# BQ25570EVO-206.net
KiCad netlist of a schematic drawn in Altium Designer
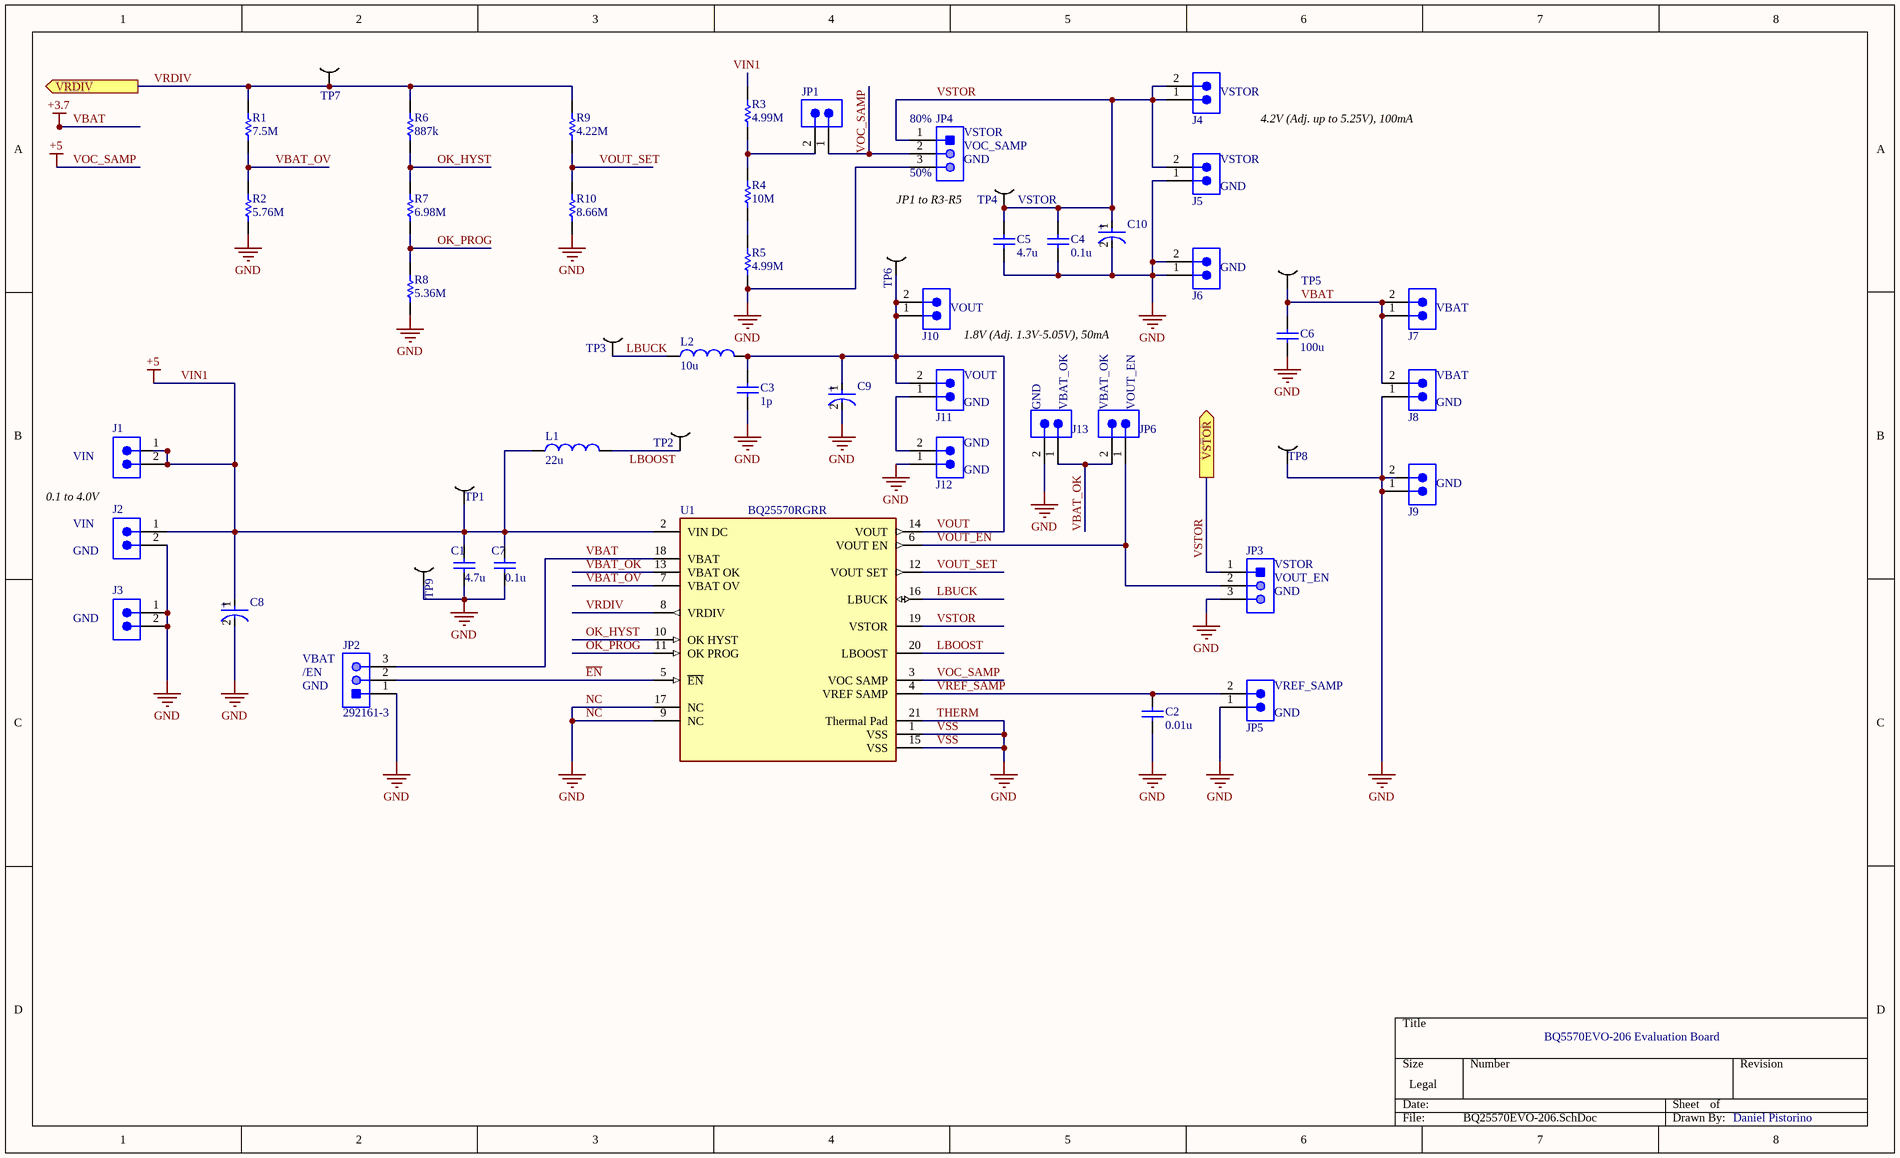
[diagram p0: BQ25570EVO-206.SchDoc]

(export (version "E")
  (design (tool "Eeschema 10.0.6"))
  (components
    (comp (ref "C1")
      (value "4.7u")
      (footprint "0603C")
      (description "Capacitor")
      (fields (field (name "Comment") "100nF") (field (name "PUBLISHER") "Altium Limited"))
      (libsource (lib "MB1136") (part "Cap"))
    )
    (comp (ref "C2")
      (value "0.01u")
      (description "Capacitor")
      (libsource (lib "Simulation Generic Components") (part "Capacitor"))
    )
    (comp (ref "C3")
      (value "1p")
      (description "Capacitor")
      (fields (field (name "Comment") "22u"))
      (libsource (lib "Simulation Generic Components") (part "Capacitor"))
    )
    (comp (ref "C4")
      (value "0.1u")
      (description "Capacitor")
      (libsource (lib "Simulation Generic Components") (part "Capacitor"))
    )
    (comp (ref "C5")
      (value "4.7u")
      (description "Capacitor")
      (libsource (lib "Simulation Generic Components") (part "Capacitor"))
    )
    (comp (ref "C6")
      (value "100u")
      (description "Capacitor")
      (libsource (lib "Simulation Generic Components") (part "Capacitor"))
    )
    (comp (ref "C7")
      (value "0.1u")
      (description "Capacitor")
      (libsource (lib "Simulation Generic Components") (part "Capacitor"))
    )
    (comp (ref "C8")
      (value "EEEFK1E470P")
      (footprint "FP-FKD-MFG")
      (description "CAP ALUM 47UF 20% 25V SMD")
      (fields (field (name "TOLERANCE") "20%") (field (name "VOLTAGE") "25V"))
      (libsource (lib "Altium Content Vault") (part "af6b09250824f1546b97fbd1c504875"))
    )
    (comp (ref "C9")
      (value "EEEFK1E470P")
      (footprint "FP-FKD-MFG")
      (description "CAP ALUM 47UF 20% 25V SMD")
      (fields (field (name "TOLERANCE") "20%") (field (name "VOLTAGE") "25V"))
      (libsource (lib "Altium Content Vault") (part "af6b09250824f1546b97fbd1c504875"))
    )
    (comp (ref "C10")
      (value "EEEFK1E470P")
      (footprint "FP-FKD-MFG")
      (description "CAP ALUM 47UF 20% 25V SMD")
      (fields (field (name "TOLERANCE") "20%") (field (name "VOLTAGE") "25V"))
      (libsource (lib "Altium Content Vault") (part "af6b09250824f1546b97fbd1c504875"))
    )
    (comp (ref "J1")
      (value "TSW-102-26-F-S")
      (footprint "SMTC-TSW-102-26-XX-S")
      (description "0.025\" SQ Post Header, Through-hole, Vertical, -55 to 125 degC, 2.54 mm Pitch, 2-Pin, Male, RoHS")
      (fields (field (name "MANUFACTURER") "Samtec"))
      (libsource (lib "Altium Content Vault") (part "SMTC-TSW-102-X-X-S-X"))
    )
    (comp (ref "J2")
      (value "TSW-102-26-F-S")
      (footprint "SMTC-TSW-102-26-XX-S")
      (description "0.025\" SQ Post Header, Through-hole, Vertical, -55 to 125 degC, 2.54 mm Pitch, 2-Pin, Male, RoHS")
      (fields (field (name "MANUFACTURER") "Samtec"))
      (libsource (lib "Altium Content Vault") (part "SMTC-TSW-102-X-X-S-X"))
    )
    (comp (ref "J3")
      (value "TSW-102-26-F-S")
      (footprint "SMTC-TSW-102-26-XX-S")
      (description "0.025\" SQ Post Header, Through-hole, Vertical, -55 to 125 degC, 2.54 mm Pitch, 2-Pin, Male, RoHS")
      (fields (field (name "MANUFACTURER") "Samtec"))
      (libsource (lib "Altium Content Vault") (part "SMTC-TSW-102-X-X-S-X"))
    )
    (comp (ref "J4")
      (value "TSW-102-26-F-S")
      (footprint "SMTC-TSW-102-26-XX-S")
      (description "0.025\" SQ Post Header, Through-hole, Vertical, -55 to 125 degC, 2.54 mm Pitch, 2-Pin, Male, RoHS")
      (fields (field (name "MANUFACTURER") "Samtec"))
      (libsource (lib "Altium Content Vault") (part "SMTC-TSW-102-X-X-S-X"))
    )
    (comp (ref "J5")
      (value "TSW-102-26-F-S")
      (footprint "SMTC-TSW-102-26-XX-S")
      (description "0.025\" SQ Post Header, Through-hole, Vertical, -55 to 125 degC, 2.54 mm Pitch, 2-Pin, Male, RoHS")
      (fields (field (name "MANUFACTURER") "Samtec"))
      (libsource (lib "Altium Content Vault") (part "SMTC-TSW-102-X-X-S-X"))
    )
    (comp (ref "J6")
      (value "TSW-102-26-F-S")
      (footprint "SMTC-TSW-102-26-XX-S")
      (description "0.025\" SQ Post Header, Through-hole, Vertical, -55 to 125 degC, 2.54 mm Pitch, 2-Pin, Male, RoHS")
      (fields (field (name "MANUFACTURER") "Samtec"))
      (libsource (lib "Altium Content Vault") (part "SMTC-TSW-102-X-X-S-X"))
    )
    (comp (ref "J7")
      (value "TSW-102-26-F-S")
      (footprint "SMTC-TSW-102-26-XX-S")
      (description "0.025\" SQ Post Header, Through-hole, Vertical, -55 to 125 degC, 2.54 mm Pitch, 2-Pin, Male, RoHS")
      (fields (field (name "MANUFACTURER") "Samtec"))
      (libsource (lib "Altium Content Vault") (part "SMTC-TSW-102-X-X-S-X"))
    )
    (comp (ref "J8")
      (value "TSW-102-26-F-S")
      (footprint "SMTC-TSW-102-26-XX-S")
      (description "0.025\" SQ Post Header, Through-hole, Vertical, -55 to 125 degC, 2.54 mm Pitch, 2-Pin, Male, RoHS")
      (fields (field (name "MANUFACTURER") "Samtec"))
      (libsource (lib "Altium Content Vault") (part "SMTC-TSW-102-X-X-S-X"))
    )
    (comp (ref "J9")
      (value "TSW-102-26-F-S")
      (footprint "SMTC-TSW-102-26-XX-S")
      (description "0.025\" SQ Post Header, Through-hole, Vertical, -55 to 125 degC, 2.54 mm Pitch, 2-Pin, Male, RoHS")
      (fields (field (name "MANUFACTURER") "Samtec"))
      (libsource (lib "Altium Content Vault") (part "SMTC-TSW-102-X-X-S-X"))
    )
    (comp (ref "J10")
      (value "TSW-102-26-F-S")
      (footprint "SMTC-TSW-102-26-XX-S")
      (description "0.025\" SQ Post Header, Through-hole, Vertical, -55 to 125 degC, 2.54 mm Pitch, 2-Pin, Male, RoHS")
      (fields (field (name "MANUFACTURER") "Samtec"))
      (libsource (lib "Altium Content Vault") (part "SMTC-TSW-102-X-X-S-X"))
    )
    (comp (ref "J11")
      (value "TSW-102-26-F-S")
      (footprint "SMTC-TSW-102-26-XX-S")
      (description "0.025\" SQ Post Header, Through-hole, Vertical, -55 to 125 degC, 2.54 mm Pitch, 2-Pin, Male, RoHS")
      (fields (field (name "MANUFACTURER") "Samtec"))
      (libsource (lib "Altium Content Vault") (part "SMTC-TSW-102-X-X-S-X"))
    )
    (comp (ref "J12")
      (value "TSW-102-26-F-S")
      (footprint "SMTC-TSW-102-26-XX-S")
      (description "0.025\" SQ Post Header, Through-hole, Vertical, -55 to 125 degC, 2.54 mm Pitch, 2-Pin, Male, RoHS")
      (fields (field (name "MANUFACTURER") "Samtec"))
      (libsource (lib "Altium Content Vault") (part "SMTC-TSW-102-X-X-S-X"))
    )
    (comp (ref "J13")
      (value "TSW-102-26-F-S")
      (footprint "SMTC-TSW-102-26-XX-S")
      (description "0.025\" SQ Post Header, Through-hole, Vertical, -55 to 125 degC, 2.54 mm Pitch, 2-Pin, Male, RoHS")
      (fields (field (name "MANUFACTURER") "Samtec"))
      (libsource (lib "Altium Content Vault") (part "SMTC-TSW-102-X-X-S-X"))
    )
    (comp (ref "JP1")
      (value "TSW-102-26-F-S")
      (footprint "SMTC-TSW-102-26-XX-S")
      (description "0.025\" SQ Post Header, Through-hole, Vertical, -55 to 125 degC, 2.54 mm Pitch, 2-Pin, Male, RoHS")
      (fields (field (name "MANUFACTURER") "Samtec"))
      (libsource (lib "Altium Content Vault") (part "SMTC-TSW-102-X-X-S-X"))
    )
    (comp (ref "JP2")
      (value "292161-3")
      (footprint "TECO-292161-3_V")
      (fields (field (name "MANUFACTURER") "TE Connectivity"))
      (libsource (lib "") (part "CN-1P-M-R3_1"))
    )
    (comp (ref "JP3")
      (value "292161-3")
      (footprint "TECO-292161-3_V")
      (fields (field (name "MANUFACTURER") "TE Connectivity"))
      (libsource (lib "Altium Content Vault") (part "CN-1P-M-R3"))
    )
    (comp (ref "JP4")
      (value "292161-3")
      (footprint "TECO-292161-3_V")
      (fields (field (name "MANUFACTURER") "TE Connectivity"))
      (libsource (lib "Altium Content Vault") (part "CN-1P-M-R3"))
    )
    (comp (ref "JP5")
      (value "TSW-102-26-F-S")
      (footprint "SMTC-TSW-102-26-XX-S")
      (description "0.025\" SQ Post Header, Through-hole, Vertical, -55 to 125 degC, 2.54 mm Pitch, 2-Pin, Male, RoHS")
      (fields (field (name "MANUFACTURER") "Samtec"))
      (libsource (lib "Altium Content Vault") (part "SMTC-TSW-102-X-X-S-X"))
    )
    (comp (ref "JP6")
      (value "TSW-102-26-F-S")
      (footprint "SMTC-TSW-102-26-XX-S")
      (description "0.025\" SQ Post Header, Through-hole, Vertical, -55 to 125 degC, 2.54 mm Pitch, 2-Pin, Male, RoHS")
      (fields (field (name "MANUFACTURER") "Samtec"))
      (libsource (lib "Altium Content Vault") (part "SMTC-TSW-102-X-X-S-X"))
    )
    (comp (ref "L1")
      (value "22u")
      (footprint "WE-RFI_0805")
      (description "744760382A WE-RFI SMT Ferrite Inductor")
      (fields (field (name "TOLERANCE") "5%"))
      (libsource (lib "Altium Content Vault") (part "Inductor - 1"))
    )
    (comp (ref "L2")
      (value "10u")
      (footprint "WE-RFI_0805")
      (description "744760382A WE-RFI SMT Ferrite Inductor")
      (fields (field (name "TOLERANCE") "5%"))
      (libsource (lib "Altium Content Vault") (part "Inductor - 1"))
    )
    (comp (ref "R1")
      (value "7.5M")
      (footprint "0603R")
      (description "Resistor")
      (fields (field (name "PUBLISHER") "Altium Limited"))
      (libsource (lib "MB1136") (part "Res1"))
    )
    (comp (ref "R2")
      (value "5.76M")
      (footprint "0603R")
      (description "Resistor")
      (fields (field (name "PUBLISHER") "Altium Limited"))
      (libsource (lib "MB1136") (part "Res1"))
    )
    (comp (ref "R3")
      (value "4.99M")
      (footprint "0603R")
      (description "Resistor")
      (fields (field (name "PUBLISHER") "Altium Limited"))
      (libsource (lib "MB1136") (part "Res1"))
    )
    (comp (ref "R4")
      (value "10M")
      (footprint "0603R")
      (description "Resistor")
      (fields (field (name "PUBLISHER") "Altium Limited"))
      (libsource (lib "MB1136") (part "Res1"))
    )
    (comp (ref "R5")
      (value "4.99M")
      (footprint "0603R")
      (description "Resistor")
      (fields (field (name "PUBLISHER") "Altium Limited"))
      (libsource (lib "MB1136") (part "Res1"))
    )
    (comp (ref "R6")
      (value "887k")
      (footprint "0603R")
      (description "Resistor")
      (fields (field (name "PUBLISHER") "Altium Limited"))
      (libsource (lib "MB1136") (part "Res1"))
    )
    (comp (ref "R7")
      (value "6.98M")
      (footprint "0603R")
      (description "Resistor")
      (fields (field (name "PUBLISHER") "Altium Limited"))
      (libsource (lib "MB1136") (part "Res1"))
    )
    (comp (ref "R8")
      (value "5.36M")
      (footprint "0603R")
      (description "Resistor")
      (fields (field (name "PUBLISHER") "Altium Limited"))
      (libsource (lib "MB1136") (part "Res1"))
    )
    (comp (ref "R9")
      (value "4.22M")
      (footprint "0603R")
      (description "Resistor")
      (fields (field (name "PUBLISHER") "Altium Limited"))
      (libsource (lib "MB1136") (part "Res1"))
    )
    (comp (ref "R10")
      (value "8.66M")
      (footprint "0603R")
      (description "Resistor")
      (fields (field (name "PUBLISHER") "Altium Limited"))
      (libsource (lib "MB1136") (part "Res1"))
    )
    (comp (ref "TP1") (value "VIN") (footprint "TestPoint") (libsource (lib "DansComponents") (part "TP?")))
    (comp (ref "TP2")
      (value "TestPoint")
      (footprint "TestPoint")
      (libsource (lib "DansComponents") (part "TP?"))
    )
    (comp (ref "TP3")
      (value "TestPoint")
      (footprint "TestPoint")
      (libsource (lib "DansComponents") (part "TP?"))
    )
    (comp (ref "TP4") (value "VSTOR") (footprint "TestPoint") (libsource (lib "DansComponents") (part "TP?")))
    (comp (ref "TP5") (value "VBAT") (footprint "TestPoint") (libsource (lib "DansComponents") (part "TP?")))
    (comp (ref "TP6")
      (value "Testpoint")
      (footprint "TestPoint")
      (libsource (lib "DansComponents") (part "TP?"))
    )
    (comp (ref "TP7")
      (value "TestPoint")
      (footprint "TestPoint")
      (libsource (lib "DansComponents") (part "TP?"))
    )
    (comp (ref "TP8")
      (value "TestPoint")
      (footprint "TestPoint")
      (libsource (lib "DansComponents") (part "TP?"))
    )
    (comp (ref "TP9")
      (value "TestPoint")
      (footprint "TestPoint")
      (libsource (lib "DansComponents") (part "TP?"))
    )
    (comp (ref "U1")
      (value "BQ25570RGRR")
      (footprint "FP-RGR0020A-MFG")
      (description "IC ENERGY HARV CTRLR BATT 20VQFN")
      (libsource (lib "Altium Content Vault") (part "27933bacb7c13f6eb3b89b25cfc7317"))
    )
  )
  (nets
    (net (code "1") (name "+3.7") (class "Default")
      (node (ref "C6") (pin "2") (pinfunction "2_2") (pintype "passive"))
      (node (ref "J7") (pin "1") (pinfunction "1_1") (pintype "passive"))
      (node (ref "J7") (pin "2") (pinfunction "2_2") (pintype "passive"))
      (node (ref "J8") (pin "2") (pinfunction "2_2") (pintype "passive"))
      (node (ref "JP2") (pin "3") (pinfunction "3_3") (pintype "passive"))
      (node (ref "TP5") (pin "TP?") (pinfunction "TP?_TP?") (pintype "passive"))
      (node (ref "U1") (pin "18") (pinfunction "VBAT_18") (pintype "power_in"))
    )
    (net (code "2") (name "+5") (class "Default")
      (node (ref "C1") (pin "2") (pinfunction "2_2") (pintype "passive"))
      (node (ref "C7") (pin "2") (pinfunction "2_2") (pintype "passive"))
      (node (ref "C8") (pin "1") (pinfunction "C_1") (pintype "passive"))
      (node (ref "J1") (pin "1") (pinfunction "1_1") (pintype "passive"))
      (node (ref "J1") (pin "2") (pinfunction "2_2") (pintype "passive"))
      (node (ref "J2") (pin "1") (pinfunction "1_1") (pintype "passive"))
      (node (ref "JP1") (pin "1") (pinfunction "1_1") (pintype "passive"))
      (node (ref "JP4") (pin "2") (pinfunction "2_2") (pintype "passive"))
      (node (ref "L1") (pin "1") (pinfunction "1_1") (pintype "passive"))
      (node (ref "R3") (pin "1") (pinfunction "1_1") (pintype "passive"))
      (node (ref "TP1") (pin "TP?") (pinfunction "TP?_TP?") (pintype "passive"))
      (node (ref "U1") (pin "2") (pinfunction "VIN_DC_2") (pintype "power_in"))
      (node (ref "U1") (pin "3") (pinfunction "VOC_SAMP_3") (pintype "power_in"))
    )
    (net (code "3") (name "/LBOOST") (class "Default")
      (node (ref "L1") (pin "2") (pinfunction "2_2") (pintype "passive"))
      (node (ref "TP2") (pin "TP?") (pinfunction "TP?_TP?") (pintype "passive"))
      (node (ref "U1") (pin "20") (pinfunction "LBOOST_20") (pintype "passive"))
    )
    (net (code "4") (name "/LBUCK") (class "Default")
      (node (ref "L2") (pin "1") (pinfunction "1_1") (pintype "passive"))
      (node (ref "TP3") (pin "TP?") (pinfunction "TP?_TP?") (pintype "passive"))
      (node (ref "U1") (pin "16") (pinfunction "LBUCK_16") (pintype "bidirectional"))
    )
    (net (code "5") (name "/OK_HYST") (class "Default")
      (node (ref "R6") (pin "2") (pinfunction "2_2") (pintype "passive"))
      (node (ref "R7") (pin "1") (pinfunction "1_1") (pintype "passive"))
      (node (ref "U1") (pin "10") (pinfunction "OK_HYST_10") (pintype "input"))
    )
    (net (code "6") (name "/OK_PROG") (class "Default")
      (node (ref "R7") (pin "2") (pinfunction "2_2") (pintype "passive"))
      (node (ref "R8") (pin "1") (pinfunction "1_1") (pintype "passive"))
      (node (ref "U1") (pin "11") (pinfunction "OK_PROG_11") (pintype "input"))
    )
    (net (code "7") (name "/VBAT_OK") (class "Default")
      (node (ref "J13") (pin "1") (pinfunction "1_1") (pintype "passive"))
      (node (ref "JP6") (pin "2") (pinfunction "2_2") (pintype "passive"))
      (node (ref "U1") (pin "13") (pinfunction "VBAT_OK_13") (pintype "power_in"))
    )
    (net (code "8") (name "/VBAT_OV") (class "Default")
      (node (ref "R1") (pin "2") (pinfunction "2_2") (pintype "passive"))
      (node (ref "R2") (pin "1") (pinfunction "1_1") (pintype "passive"))
      (node (ref "U1") (pin "7") (pinfunction "VBAT_OV_7") (pintype "power_in"))
    )
    (net (code "9") (name "/VOUT") (class "Default")
      (node (ref "C3") (pin "2") (pinfunction "2_2") (pintype "passive"))
      (node (ref "C9") (pin "1") (pinfunction "C_1") (pintype "passive"))
      (node (ref "J10") (pin "1") (pinfunction "1_1") (pintype "passive"))
      (node (ref "J10") (pin "2") (pinfunction "2_2") (pintype "passive"))
      (node (ref "J11") (pin "2") (pinfunction "2_2") (pintype "passive"))
      (node (ref "L2") (pin "2") (pinfunction "2_2") (pintype "passive"))
      (node (ref "TP6") (pin "TP?") (pinfunction "TP?_TP?") (pintype "passive"))
      (node (ref "U1") (pin "14") (pinfunction "VOUT_14") (pintype "output"))
    )
    (net (code "10") (name "/VOUT_EN") (class "Default")
      (node (ref "JP3") (pin "2") (pinfunction "2_2") (pintype "passive"))
      (node (ref "JP6") (pin "1") (pinfunction "1_1") (pintype "passive"))
      (node (ref "U1") (pin "6") (pinfunction "VOUT_EN_6") (pintype "output"))
    )
    (net (code "11") (name "/VOUT_SET") (class "Default")
      (node (ref "R10") (pin "1") (pinfunction "1_1") (pintype "passive"))
      (node (ref "R9") (pin "2") (pinfunction "2_2") (pintype "passive"))
      (node (ref "U1") (pin "12") (pinfunction "VOUT_SET_12") (pintype "output"))
    )
    (net (code "12") (name "/VRDIV") (class "Default")
      (node (ref "R1") (pin "1") (pinfunction "1_1") (pintype "passive"))
      (node (ref "R6") (pin "1") (pinfunction "1_1") (pintype "passive"))
      (node (ref "R9") (pin "1") (pinfunction "1_1") (pintype "passive"))
      (node (ref "TP7") (pin "TP?") (pinfunction "TP?_TP?") (pintype "passive"))
      (node (ref "U1") (pin "8") (pinfunction "VRDIV_8") (pintype "output"))
    )
    (net (code "13") (name "/VREF_SAMP") (class "Default")
      (node (ref "C2") (pin "2") (pinfunction "2_2") (pintype "passive"))
      (node (ref "JP5") (pin "2") (pinfunction "2_2") (pintype "passive"))
      (node (ref "U1") (pin "4") (pinfunction "VREF_SAMP_4") (pintype "passive"))
    )
    (net (code "14") (name "/VSTOR") (class "Default")
      (node (ref "C10") (pin "1") (pinfunction "C_1") (pintype "passive"))
      (node (ref "C4") (pin "2") (pinfunction "2_2") (pintype "passive"))
      (node (ref "C5") (pin "2") (pinfunction "2_2") (pintype "passive"))
      (node (ref "J4") (pin "1") (pinfunction "1_1") (pintype "passive"))
      (node (ref "J4") (pin "2") (pinfunction "2_2") (pintype "passive"))
      (node (ref "J5") (pin "2") (pinfunction "2_2") (pintype "passive"))
      (node (ref "JP3") (pin "1") (pinfunction "1_1") (pintype "passive"))
      (node (ref "JP4") (pin "1") (pinfunction "1_1") (pintype "passive"))
      (node (ref "TP4") (pin "TP?") (pinfunction "TP?_TP?") (pintype "passive"))
      (node (ref "U1") (pin "19") (pinfunction "VSTOR_19") (pintype "passive"))
    )
    (net (code "15") (name "/~{EN}") (class "Default")
      (node (ref "JP2") (pin "2") (pinfunction "2_2") (pintype "passive"))
      (node (ref "U1") (pin "5") (pinfunction "~{EN}_5") (pintype "input"))
    )
    (net (code "16") (name "GND") (class "Default")
      (node (ref "C1") (pin "1") (pinfunction "1_1") (pintype "passive"))
      (node (ref "C10") (pin "2") (pinfunction "A_2") (pintype "passive"))
      (node (ref "C2") (pin "1") (pinfunction "1_1") (pintype "passive"))
      (node (ref "C3") (pin "1") (pinfunction "1_1") (pintype "passive"))
      (node (ref "C4") (pin "1") (pinfunction "1_1") (pintype "passive"))
      (node (ref "C5") (pin "1") (pinfunction "1_1") (pintype "passive"))
      (node (ref "C6") (pin "1") (pinfunction "1_1") (pintype "passive"))
      (node (ref "C7") (pin "1") (pinfunction "1_1") (pintype "passive"))
      (node (ref "C8") (pin "2") (pinfunction "A_2") (pintype "passive"))
      (node (ref "C9") (pin "2") (pinfunction "A_2") (pintype "passive"))
      (node (ref "J12") (pin "1") (pinfunction "1_1") (pintype "passive"))
      (node (ref "J13") (pin "2") (pinfunction "2_2") (pintype "passive"))
      (node (ref "J2") (pin "2") (pinfunction "2_2") (pintype "passive"))
      (node (ref "J3") (pin "1") (pinfunction "1_1") (pintype "passive"))
      (node (ref "J3") (pin "2") (pinfunction "2_2") (pintype "passive"))
      (node (ref "J5") (pin "1") (pinfunction "1_1") (pintype "passive"))
      (node (ref "J6") (pin "1") (pinfunction "1_1") (pintype "passive"))
      (node (ref "J6") (pin "2") (pinfunction "2_2") (pintype "passive"))
      (node (ref "J8") (pin "1") (pinfunction "1_1") (pintype "passive"))
      (node (ref "J9") (pin "1") (pinfunction "1_1") (pintype "passive"))
      (node (ref "J9") (pin "2") (pinfunction "2_2") (pintype "passive"))
      (node (ref "JP2") (pin "1") (pinfunction "1_1") (pintype "passive"))
      (node (ref "JP3") (pin "3") (pinfunction "3_3") (pintype "passive"))
      (node (ref "JP4") (pin "3") (pinfunction "3_3") (pintype "passive"))
      (node (ref "JP5") (pin "1") (pinfunction "1_1") (pintype "passive"))
      (node (ref "R10") (pin "2") (pinfunction "2_2") (pintype "passive"))
      (node (ref "R2") (pin "2") (pinfunction "2_2") (pintype "passive"))
      (node (ref "R5") (pin "2") (pinfunction "2_2") (pintype "passive"))
      (node (ref "R8") (pin "2") (pinfunction "2_2") (pintype "passive"))
      (node (ref "TP8") (pin "TP?") (pinfunction "TP?_TP?") (pintype "passive"))
      (node (ref "TP9") (pin "TP?") (pinfunction "TP?_TP?") (pintype "passive"))
      (node (ref "U1") (pin "1") (pinfunction "VSS_1") (pintype "power_in"))
      (node (ref "U1") (pin "15") (pinfunction "VSS_15") (pintype "power_in"))
      (node (ref "U1") (pin "17") (pinfunction "NC_17") (pintype "passive"))
      (node (ref "U1") (pin "21") (pinfunction "Thermal_Pad_21") (pintype "passive"))
      (node (ref "U1") (pin "9") (pinfunction "NC_9") (pintype "passive"))
    )
    (net (code "17") (name "Net-(J11-Pad1)") (class "Default")
      (node (ref "J11") (pin "1") (pinfunction "1_1") (pintype "passive"))
      (node (ref "J12") (pin "2") (pinfunction "2_2") (pintype "passive"))
    )
    (net (code "18") (name "Net-(JP1-Pad2)") (class "Default")
      (node (ref "JP1") (pin "2") (pinfunction "2_2") (pintype "passive"))
      (node (ref "R3") (pin "2") (pinfunction "2_2") (pintype "passive"))
      (node (ref "R4") (pin "1") (pinfunction "1_1") (pintype "passive"))
    )
    (net (code "19") (name "Net-(R4-Pad2)") (class "Default")
      (node (ref "R4") (pin "2") (pinfunction "2_2") (pintype "passive"))
      (node (ref "R5") (pin "1") (pinfunction "1_1") (pintype "passive"))
    )
  )
)
